# ethusb.net
KiCad netlist of a schematic drawn in Altium Designer
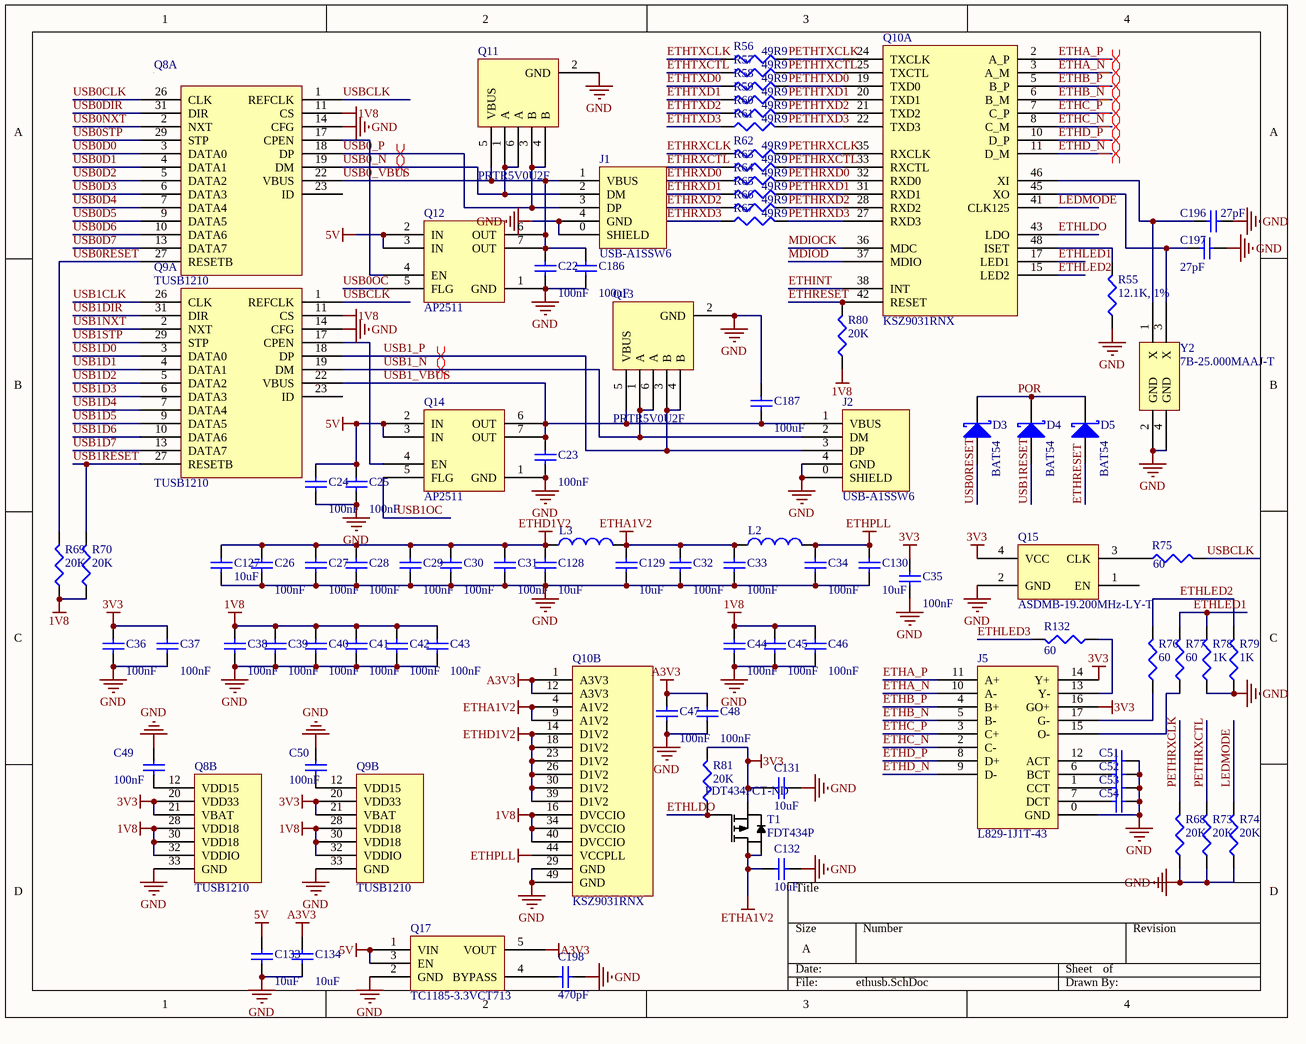
[diagram p0: ethusb.SchDoc]

(export (version "E")
  (design (tool "Eeschema 10.0.6"))
  (components
    (comp (ref "C22")
      (value "100nF")
      (footprint "CAPC1005X06L")
      (description "Capacitor")
      (fields (field (name "Comment") "Cap") (field (name "PUBLISHER") "Altium Limited"))
      (libsource (lib "Miscellaneous Devices") (part "Cap"))
    )
    (comp (ref "C23")
      (value "100nF")
      (footprint "CAPC1005X06L")
      (description "Capacitor")
      (fields (field (name "Comment") "Cap") (field (name "PUBLISHER") "Altium Limited"))
      (libsource (lib "Miscellaneous Devices") (part "Cap"))
    )
    (comp (ref "C24")
      (value "100nF")
      (footprint "CAPC1005X06L")
      (description "Capacitor")
      (fields (field (name "Comment") "Cap") (field (name "PUBLISHER") "Altium Limited"))
      (libsource (lib "Miscellaneous Devices") (part "Cap"))
    )
    (comp (ref "C25")
      (value "100nF")
      (footprint "CAPC1005X06L")
      (description "Capacitor")
      (fields (field (name "Comment") "Cap") (field (name "PUBLISHER") "Altium Limited"))
      (libsource (lib "Miscellaneous Devices") (part "Cap"))
    )
    (comp (ref "C26")
      (value "100nF")
      (footprint "CAPC1005X06L")
      (description "Capacitor")
      (fields (field (name "Comment") "Cap") (field (name "PUBLISHER") "Altium Limited"))
      (libsource (lib "Miscellaneous Devices") (part "Cap"))
    )
    (comp (ref "C27")
      (value "100nF")
      (footprint "CAPC1005X06L")
      (description "Capacitor")
      (fields (field (name "Comment") "Cap") (field (name "PUBLISHER") "Altium Limited"))
      (libsource (lib "Miscellaneous Devices") (part "Cap"))
    )
    (comp (ref "C28")
      (value "100nF")
      (footprint "CAPC1005X06L")
      (description "Capacitor")
      (fields (field (name "Comment") "Cap") (field (name "PUBLISHER") "Altium Limited"))
      (libsource (lib "Miscellaneous Devices") (part "Cap"))
    )
    (comp (ref "C29")
      (value "100nF")
      (footprint "CAPC1005X06L")
      (description "Capacitor")
      (fields (field (name "Comment") "Cap") (field (name "PUBLISHER") "Altium Limited"))
      (libsource (lib "Miscellaneous Devices") (part "Cap"))
    )
    (comp (ref "C30")
      (value "100nF")
      (footprint "CAPC1005X06L")
      (description "Capacitor")
      (fields (field (name "Comment") "Cap") (field (name "PUBLISHER") "Altium Limited"))
      (libsource (lib "Miscellaneous Devices") (part "Cap"))
    )
    (comp (ref "C31")
      (value "100nF")
      (footprint "CAPC1005X06L")
      (description "Capacitor")
      (fields (field (name "Comment") "Cap") (field (name "PUBLISHER") "Altium Limited"))
      (libsource (lib "Miscellaneous Devices") (part "Cap"))
    )
    (comp (ref "C32")
      (value "100nF")
      (footprint "CAPC1005X06L")
      (description "Capacitor")
      (fields (field (name "Comment") "Cap") (field (name "PUBLISHER") "Altium Limited"))
      (libsource (lib "Miscellaneous Devices") (part "Cap"))
    )
    (comp (ref "C33")
      (value "100nF")
      (footprint "CAPC1005X06L")
      (description "Capacitor")
      (fields (field (name "Comment") "Cap") (field (name "PUBLISHER") "Altium Limited"))
      (libsource (lib "Miscellaneous Devices") (part "Cap"))
    )
    (comp (ref "C34")
      (value "100nF")
      (footprint "CAPC1005X06L")
      (description "Capacitor")
      (fields (field (name "Comment") "Cap") (field (name "PUBLISHER") "Altium Limited"))
      (libsource (lib "Miscellaneous Devices") (part "Cap"))
    )
    (comp (ref "C35")
      (value "100nF")
      (footprint "CAPC1005X06L")
      (description "Capacitor")
      (fields (field (name "Comment") "Cap") (field (name "PUBLISHER") "Altium Limited"))
      (libsource (lib "Miscellaneous Devices") (part "Cap"))
    )
    (comp (ref "C36")
      (value "100nF")
      (footprint "CAPC1005X06L")
      (description "Capacitor")
      (fields (field (name "Comment") "Cap") (field (name "PUBLISHER") "Altium Limited"))
      (libsource (lib "Miscellaneous Devices") (part "Cap"))
    )
    (comp (ref "C37")
      (value "100nF")
      (footprint "CAPC1005X06L")
      (description "Capacitor")
      (fields (field (name "Comment") "Cap") (field (name "PUBLISHER") "Altium Limited"))
      (libsource (lib "Miscellaneous Devices") (part "Cap"))
    )
    (comp (ref "C38")
      (value "100nF")
      (footprint "CAPC1005X06L")
      (description "Capacitor")
      (fields (field (name "Comment") "Cap") (field (name "PUBLISHER") "Altium Limited"))
      (libsource (lib "Miscellaneous Devices") (part "Cap"))
    )
    (comp (ref "C39")
      (value "100nF")
      (footprint "CAPC1005X06L")
      (description "Capacitor")
      (fields (field (name "Comment") "Cap") (field (name "PUBLISHER") "Altium Limited"))
      (libsource (lib "Miscellaneous Devices") (part "Cap"))
    )
    (comp (ref "C40")
      (value "100nF")
      (footprint "CAPC1005X06L")
      (description "Capacitor")
      (fields (field (name "Comment") "Cap") (field (name "PUBLISHER") "Altium Limited"))
      (libsource (lib "Miscellaneous Devices") (part "Cap"))
    )
    (comp (ref "C41")
      (value "100nF")
      (footprint "CAPC1005X06L")
      (description "Capacitor")
      (fields (field (name "Comment") "Cap") (field (name "PUBLISHER") "Altium Limited"))
      (libsource (lib "Miscellaneous Devices") (part "Cap"))
    )
    (comp (ref "C42")
      (value "100nF")
      (footprint "CAPC1005X06L")
      (description "Capacitor")
      (fields (field (name "Comment") "Cap") (field (name "PUBLISHER") "Altium Limited"))
      (libsource (lib "Miscellaneous Devices") (part "Cap"))
    )
    (comp (ref "C43")
      (value "100nF")
      (footprint "CAPC1005X06L")
      (description "Capacitor")
      (fields (field (name "Comment") "Cap") (field (name "PUBLISHER") "Altium Limited"))
      (libsource (lib "Miscellaneous Devices") (part "Cap"))
    )
    (comp (ref "C44")
      (value "100nF")
      (footprint "CAPC1005X06L")
      (description "Capacitor")
      (fields (field (name "Comment") "Cap") (field (name "PUBLISHER") "Altium Limited"))
      (libsource (lib "Miscellaneous Devices") (part "Cap"))
    )
    (comp (ref "C45")
      (value "100nF")
      (footprint "CAPC1005X06L")
      (description "Capacitor")
      (fields (field (name "Comment") "Cap") (field (name "PUBLISHER") "Altium Limited"))
      (libsource (lib "Miscellaneous Devices") (part "Cap"))
    )
    (comp (ref "C46")
      (value "100nF")
      (footprint "CAPC1005X06L")
      (description "Capacitor")
      (fields (field (name "Comment") "Cap") (field (name "PUBLISHER") "Altium Limited"))
      (libsource (lib "Miscellaneous Devices") (part "Cap"))
    )
    (comp (ref "C47")
      (value "100nF")
      (footprint "CAPC1005X06L")
      (description "Capacitor")
      (fields (field (name "Comment") "Cap") (field (name "PUBLISHER") "Altium Limited"))
      (libsource (lib "Miscellaneous Devices") (part "Cap"))
    )
    (comp (ref "C48")
      (value "100nF")
      (footprint "CAPC1005X06L")
      (description "Capacitor")
      (fields (field (name "Comment") "Cap") (field (name "PUBLISHER") "Altium Limited"))
      (libsource (lib "Miscellaneous Devices") (part "Cap"))
    )
    (comp (ref "C49")
      (value "100nF")
      (footprint "CAPC1005X06L")
      (description "Capacitor")
      (fields (field (name "Comment") "Cap") (field (name "PUBLISHER") "Altium Limited"))
      (libsource (lib "Miscellaneous Devices") (part "Cap"))
    )
    (comp (ref "C50")
      (value "100nF")
      (footprint "CAPC1005X06L")
      (description "Capacitor")
      (fields (field (name "Comment") "Cap") (field (name "PUBLISHER") "Altium Limited"))
      (libsource (lib "Miscellaneous Devices") (part "Cap"))
    )
    (comp (ref "C51")
      (value "Cap")
      (footprint "CAPC1005X06L")
      (description "Capacitor")
      (fields (field (name "PUBLISHER") "Altium Limited"))
      (libsource (lib "Miscellaneous Devices") (part "Cap"))
    )
    (comp (ref "C52")
      (value "Cap")
      (footprint "CAPC1005X06L")
      (description "Capacitor")
      (fields (field (name "PUBLISHER") "Altium Limited"))
      (libsource (lib "Miscellaneous Devices") (part "Cap"))
    )
    (comp (ref "C53")
      (value "Cap")
      (footprint "CAPC1005X06L")
      (description "Capacitor")
      (fields (field (name "PUBLISHER") "Altium Limited"))
      (libsource (lib "Miscellaneous Devices") (part "Cap"))
    )
    (comp (ref "C54")
      (value "Cap")
      (footprint "CAPC1005X06L")
      (description "Capacitor")
      (fields (field (name "PUBLISHER") "Altium Limited"))
      (libsource (lib "Miscellaneous Devices") (part "Cap"))
    )
    (comp (ref "C127")
      (value "10uF")
      (footprint "CAPC1608X90N")
      (description "Capacitor")
      (fields (field (name "Comment") "GRM188R60G106ME47") (field (name "PUBLISHER") "Altium Limited"))
      (libsource (lib "Miscellaneous Devices") (part "Cap"))
    )
    (comp (ref "C128")
      (value "10uF")
      (footprint "CAPC1608X90N")
      (description "Capacitor")
      (fields (field (name "Comment") "GRM188R60G106ME47") (field (name "PUBLISHER") "Altium Limited"))
      (libsource (lib "Miscellaneous Devices") (part "Cap"))
    )
    (comp (ref "C129")
      (value "10uF")
      (footprint "CAPC1608X90N")
      (description "Capacitor")
      (fields (field (name "Comment") "GRM188R60G106ME47") (field (name "PUBLISHER") "Altium Limited"))
      (libsource (lib "Miscellaneous Devices") (part "Cap"))
    )
    (comp (ref "C130")
      (value "10uF")
      (footprint "CAPC1608X90N")
      (description "Capacitor")
      (fields (field (name "Comment") "GRM188R60G106ME47") (field (name "PUBLISHER") "Altium Limited"))
      (libsource (lib "Miscellaneous Devices") (part "Cap"))
    )
    (comp (ref "C131")
      (value "10uF")
      (footprint "CAPC1608X90N")
      (description "Capacitor")
      (fields (field (name "Comment") "GRM188R60G106ME47") (field (name "PUBLISHER") "Altium Limited"))
      (libsource (lib "Miscellaneous Devices") (part "Cap"))
    )
    (comp (ref "C132")
      (value "10uF")
      (footprint "CAPC1608X90N")
      (description "Capacitor")
      (fields (field (name "Comment") "GRM188R60G106ME47") (field (name "PUBLISHER") "Altium Limited"))
      (libsource (lib "Miscellaneous Devices") (part "Cap"))
    )
    (comp (ref "C133")
      (value "10uF")
      (footprint "CAPC1608X90N")
      (description "Capacitor")
      (fields (field (name "Comment") "GRM188R60G106ME47") (field (name "PUBLISHER") "Altium Limited"))
      (libsource (lib "Miscellaneous Devices") (part "Cap"))
    )
    (comp (ref "C134")
      (value "10uF")
      (footprint "CAPC1608X90N")
      (description "Capacitor")
      (fields (field (name "Comment") "GRM188R60G106ME47") (field (name "PUBLISHER") "Altium Limited"))
      (libsource (lib "Miscellaneous Devices") (part "Cap"))
    )
    (comp (ref "C186")
      (value "100uF")
      (footprint "CAPC3225X220N")
      (description "Capacitor")
      (fields (field (name "Comment") "GRM31CR60J107ME39L") (field (name "PUBLISHER") "Altium Limited"))
      (libsource (lib "Miscellaneous Devices") (part "Cap"))
    )
    (comp (ref "C187")
      (value "100uF")
      (footprint "CAPC3225X220N")
      (description "Capacitor")
      (fields (field (name "Comment") "GRM31CR60J107ME39L") (field (name "PUBLISHER") "Altium Limited"))
      (libsource (lib "Miscellaneous Devices") (part "Cap"))
    )
    (comp (ref "C196")
      (value "27pF")
      (footprint "CAPC1608X90N")
      (description "Capacitor")
      (fields (field (name "Comment") "CL10C270JB8NNNC") (field (name "PUBLISHER") "Altium Limited"))
      (libsource (lib "Miscellaneous Devices") (part "Cap"))
    )
    (comp (ref "C197")
      (value "27pF")
      (footprint "CAPC1608X90N")
      (description "Capacitor")
      (fields (field (name "Comment") "CL10C270JB8NNNC") (field (name "PUBLISHER") "Altium Limited"))
      (libsource (lib "Miscellaneous Devices") (part "Cap"))
    )
    (comp (ref "C198")
      (value "470pF")
      (footprint "CAPC1608X90N")
      (description "Capacitor")
      (fields (field (name "Comment") "CL10C471JB8NCNC") (field (name "PUBLISHER") "Altium Limited"))
      (libsource (lib "Miscellaneous Devices") (part "Cap"))
    )
    (comp (ref "D3")
      (value "BAT54")
      (footprint "BAT54")
      (description "Schottky Diode")
      (fields (field (name "PUBLISHER") "Altium Limited"))
      (libsource (lib "Miscellaneous Devices") (part "D Schottky"))
    )
    (comp (ref "D4")
      (value "BAT54")
      (footprint "BAT54")
      (description "Schottky Diode")
      (fields (field (name "PUBLISHER") "Altium Limited"))
      (libsource (lib "Miscellaneous Devices") (part "D Schottky"))
    )
    (comp (ref "D5")
      (value "BAT54")
      (footprint "BAT54")
      (description "Schottky Diode")
      (fields (field (name "PUBLISHER") "Altium Limited"))
      (libsource (lib "Miscellaneous Devices") (part "D Schottky"))
    )
    (comp (ref "J1") (value "USB-A1SSW6") (footprint "USB-A1SSW6") (libsource (lib "schlib") (part "USB")))
    (comp (ref "J2") (value "USB-A1SSW6") (footprint "USB-A1SSW6") (libsource (lib "schlib") (part "USB")))
    (comp (ref "J5")
      (value "L829-1J1T-43")
      (footprint "ETH-L829-1J1T-43")
      (libsource (lib "schlib") (part "ETH"))
    )
    (comp (ref "L2")
      (value "BLM18SG121TN1")
      (footprint "CAPC1608X90N")
      (description "Inductor")
      (fields (field (name "PUBLISHER") "Altium Limited"))
      (libsource (lib "Miscellaneous Devices") (part "Inductor"))
    )
    (comp (ref "L3")
      (value "BLM18SG121TN1")
      (footprint "CAPC1608X90N")
      (description "Inductor")
      (fields (field (name "PUBLISHER") "Altium Limited"))
      (libsource (lib "Miscellaneous Devices") (part "Inductor"))
    )
    (comp (ref "Q8")
      (value "TUSB1210")
      (footprint "QFN50P500X500X80_HS-33N")
      (libsource (lib "schlib") (part "TUSB1210"))
    )
    (comp (ref "Q9")
      (value "TUSB1210")
      (footprint "QFN50P500X500X80_HS-33N")
      (libsource (lib "schlib") (part "TUSB1210"))
    )
    (comp (ref "Q10") (value "KSZ9031RNX") (libsource (lib "schlib") (part "KSZ9031RNX")))
    (comp (ref "Q11")
      (value "PRTR5V0U2F")
      (footprint "SOT886")
      (libsource (lib "schlib") (part "PRTR5V0U2F"))
    )
    (comp (ref "Q12")
      (value "AP2511")
      (footprint "SOIC127P600X175-8AN")
      (libsource (lib "schlib") (part "AP2511"))
    )
    (comp (ref "Q13")
      (value "PRTR5V0U2F")
      (footprint "SOT886")
      (libsource (lib "schlib") (part "PRTR5V0U2F"))
    )
    (comp (ref "Q14")
      (value "AP2511")
      (footprint "SOIC127P600X175-8AN")
      (libsource (lib "schlib") (part "AP2511"))
    )
    (comp (ref "Q15")
      (value "ASDMB-19.200MHz-LY-T")
      (footprint "ASDMB")
      (libsource (lib "schlib") (part "osc"))
    )
    (comp (ref "Q17")
      (value "TC1185-3.3VCT713")
      (footprint "SOT23-5")
      (libsource (lib "schlib") (part "LDO"))
    )
    (comp (ref "R55")
      (value "12.1K, 1%")
      (footprint "J1-0603")
      (description "Resistor")
      (fields (field (name "Comment") "RC1608F1212CS") (field (name "PUBLISHER") "Altium Limited"))
      (libsource (lib "Miscellaneous Devices") (part "Res3"))
    )
    (comp (ref "R56")
      (value "49R9")
      (footprint "CAPC1005X06L")
      (description "Resistor")
      (fields (field (name "Comment") "RC1005F49R9CS") (field (name "PUBLISHER") "Altium Limited"))
      (libsource (lib "Miscellaneous Devices") (part "Res3"))
    )
    (comp (ref "R57")
      (value "49R9")
      (footprint "CAPC1005X06L")
      (description "Resistor")
      (fields (field (name "Comment") "RC1005F49R9CS") (field (name "PUBLISHER") "Altium Limited"))
      (libsource (lib "Miscellaneous Devices") (part "Res3"))
    )
    (comp (ref "R58")
      (value "49R9")
      (footprint "CAPC1005X06L")
      (description "Resistor")
      (fields (field (name "Comment") "RC1005F49R9CS") (field (name "PUBLISHER") "Altium Limited"))
      (libsource (lib "Miscellaneous Devices") (part "Res3"))
    )
    (comp (ref "R59")
      (value "49R9")
      (footprint "CAPC1005X06L")
      (description "Resistor")
      (fields (field (name "Comment") "RC1005F49R9CS") (field (name "PUBLISHER") "Altium Limited"))
      (libsource (lib "Miscellaneous Devices") (part "Res3"))
    )
    (comp (ref "R60")
      (value "49R9")
      (footprint "CAPC1005X06L")
      (description "Resistor")
      (fields (field (name "Comment") "RC1005F49R9CS") (field (name "PUBLISHER") "Altium Limited"))
      (libsource (lib "Miscellaneous Devices") (part "Res3"))
    )
    (comp (ref "R61")
      (value "49R9")
      (footprint "CAPC1005X06L")
      (description "Resistor")
      (fields (field (name "Comment") "RC1005F49R9CS") (field (name "PUBLISHER") "Altium Limited"))
      (libsource (lib "Miscellaneous Devices") (part "Res3"))
    )
    (comp (ref "R62")
      (value "49R9")
      (footprint "CAPC1005X06L")
      (description "Resistor")
      (fields (field (name "Comment") "RC1005F49R9CS") (field (name "PUBLISHER") "Altium Limited"))
      (libsource (lib "Miscellaneous Devices") (part "Res3"))
    )
    (comp (ref "R63")
      (value "49R9")
      (footprint "CAPC1005X06L")
      (description "Resistor")
      (fields (field (name "Comment") "RC1005F49R9CS") (field (name "PUBLISHER") "Altium Limited"))
      (libsource (lib "Miscellaneous Devices") (part "Res3"))
    )
    (comp (ref "R64")
      (value "49R9")
      (footprint "CAPC1005X06L")
      (description "Resistor")
      (fields (field (name "Comment") "RC1005F49R9CS") (field (name "PUBLISHER") "Altium Limited"))
      (libsource (lib "Miscellaneous Devices") (part "Res3"))
    )
    (comp (ref "R65")
      (value "49R9")
      (footprint "CAPC1005X06L")
      (description "Resistor")
      (fields (field (name "Comment") "RC1005F49R9CS") (field (name "PUBLISHER") "Altium Limited"))
      (libsource (lib "Miscellaneous Devices") (part "Res3"))
    )
    (comp (ref "R66")
      (value "49R9")
      (footprint "CAPC1005X06L")
      (description "Resistor")
      (fields (field (name "Comment") "RC1005F49R9CS") (field (name "PUBLISHER") "Altium Limited"))
      (libsource (lib "Miscellaneous Devices") (part "Res3"))
    )
    (comp (ref "R67")
      (value "49R9")
      (footprint "CAPC1005X06L")
      (description "Resistor")
      (fields (field (name "Comment") "RC1005F49R9CS") (field (name "PUBLISHER") "Altium Limited"))
      (libsource (lib "Miscellaneous Devices") (part "Res3"))
    )
    (comp (ref "R68")
      (value "20K")
      (footprint "J1-0603")
      (description "Resistor")
      (fields (field (name "Comment") "RC1608F203CS") (field (name "PUBLISHER") "Altium Limited"))
      (libsource (lib "Miscellaneous Devices") (part "Res3"))
    )
    (comp (ref "R69")
      (value "20K")
      (footprint "J1-0603")
      (description "Resistor")
      (fields (field (name "Comment") "RC1608F203CS") (field (name "PUBLISHER") "Altium Limited"))
      (libsource (lib "Miscellaneous Devices") (part "Res3"))
    )
    (comp (ref "R70")
      (value "20K")
      (footprint "J1-0603")
      (description "Resistor")
      (fields (field (name "Comment") "RC1608F203CS") (field (name "PUBLISHER") "Altium Limited"))
      (libsource (lib "Miscellaneous Devices") (part "Res3"))
    )
    (comp (ref "R73")
      (value "20K")
      (footprint "J1-0603")
      (description "Resistor")
      (fields (field (name "Comment") "RC1608F203CS") (field (name "PUBLISHER") "Altium Limited"))
      (libsource (lib "Miscellaneous Devices") (part "Res3"))
    )
    (comp (ref "R74")
      (value "20K")
      (footprint "J1-0603")
      (description "Resistor")
      (fields (field (name "Comment") "RC1608F203CS") (field (name "PUBLISHER") "Altium Limited"))
      (libsource (lib "Miscellaneous Devices") (part "Res3"))
    )
    (comp (ref "R75")
      (value "60")
      (footprint "J1-0603")
      (description "Resistor")
      (fields (field (name "Comment") "RC1608F60R4CS"))
      (libsource (lib "Miscellaneous Devices") (part "Res3"))
    )
    (comp (ref "R76")
      (value "60")
      (footprint "J1-0603")
      (description "Resistor")
      (fields (field (name "Comment") "RC1608F60R4CS"))
      (libsource (lib "Miscellaneous Devices") (part "Res3"))
    )
    (comp (ref "R77")
      (value "60")
      (footprint "J1-0603")
      (description "Resistor")
      (fields (field (name "Comment") "RC1608F60R4CS"))
      (libsource (lib "Miscellaneous Devices") (part "Res3"))
    )
    (comp (ref "R78")
      (value "1K")
      (footprint "J1-0603")
      (description "Resistor")
      (fields (field (name "Comment") "RC1608J102CS"))
      (libsource (lib "Miscellaneous Devices") (part "Res3"))
    )
    (comp (ref "R79")
      (value "1K")
      (footprint "J1-0603")
      (description "Resistor")
      (fields (field (name "Comment") "RC1608J102CS"))
      (libsource (lib "Miscellaneous Devices") (part "Res3"))
    )
    (comp (ref "R80")
      (value "20K")
      (footprint "J1-0603")
      (description "Resistor")
      (fields (field (name "Comment") "RC1608F203CS"))
      (libsource (lib "Miscellaneous Devices") (part "Res3"))
    )
    (comp (ref "R81")
      (value "20K")
      (footprint "J1-0603")
      (description "Resistor")
      (fields (field (name "Comment") "RC1608F203CS"))
      (libsource (lib "Miscellaneous Devices") (part "Res3"))
    )
    (comp (ref "R132")
      (value "60")
      (footprint "J1-0603")
      (description "Resistor")
      (fields (field (name "Comment") "RC1608F60R4CS"))
      (libsource (lib "Miscellaneous Devices") (part "Res3"))
    )
    (comp (ref "T1")
      (value "FDT434P")
      (fields (field (name "SUPPLIER PART NUMBER 1") "FDT434PCT-ND"))
      (libsource (lib "schlib") (part "PMOS4"))
    )
    (comp (ref "Y2") (value "7B-25.000MAAJ-T") (footprint "XTAL") (libsource (lib "schlib") (part "XTAL")))
  )
  (nets
    (net (code "1") (name "/ETHA_N") (class "Default")
      (node (ref "J5") (pin "10") (pinfunction "A-_10") (pintype "passive"))
      (node (ref "Q10") (pin "3") (pinfunction "A_M_3") (pintype "passive"))
    )
    (net (code "2") (name "/ETHA_P") (class "Default")
      (node (ref "J5") (pin "11") (pinfunction "A+_11") (pintype "passive"))
      (node (ref "Q10") (pin "2") (pinfunction "A_P_2") (pintype "passive"))
    )
    (net (code "3") (name "/ETHB_N") (class "Default")
      (node (ref "J5") (pin "5") (pinfunction "B-_5") (pintype "passive"))
      (node (ref "Q10") (pin "6") (pinfunction "B_M_6") (pintype "passive"))
    )
    (net (code "4") (name "/ETHB_P") (class "Default")
      (node (ref "J5") (pin "4") (pinfunction "B+_4") (pintype "passive"))
      (node (ref "Q10") (pin "5") (pinfunction "B_P_5") (pintype "passive"))
    )
    (net (code "5") (name "/ETHC_N") (class "Default")
      (node (ref "J5") (pin "2") (pinfunction "C-_2") (pintype "passive"))
      (node (ref "Q10") (pin "8") (pinfunction "C_M_8") (pintype "passive"))
    )
    (net (code "6") (name "/ETHC_P") (class "Default")
      (node (ref "J5") (pin "3") (pinfunction "C+_3") (pintype "passive"))
      (node (ref "Q10") (pin "7") (pinfunction "C_P_7") (pintype "passive"))
    )
    (net (code "7") (name "/ETHD_N") (class "Default")
      (node (ref "J5") (pin "9") (pinfunction "D-_9") (pintype "passive"))
      (node (ref "Q10") (pin "11") (pinfunction "D_M_11") (pintype "passive"))
    )
    (net (code "8") (name "/ETHD_P") (class "Default")
      (node (ref "J5") (pin "8") (pinfunction "D+_8") (pintype "passive"))
      (node (ref "Q10") (pin "10") (pinfunction "D_P_10") (pintype "passive"))
    )
    (net (code "9") (name "/ETHINT") (class "Default")
      (node (ref "Q10") (pin "38") (pinfunction "INT_38") (pintype "passive"))
    )
    (net (code "10") (name "/ETHLDO") (class "Default")
      (node (ref "Q10") (pin "43") (pinfunction "LDO_43") (pintype "passive"))
      (node (ref "R81") (pin "1") (pinfunction "1_1") (pintype "passive"))
      (node (ref "T1") (pin "1") (pinfunction "G_1") (pintype "passive"))
    )
    (net (code "11") (name "/ETHLED1") (class "Default")
      (node (ref "Q10") (pin "17") (pinfunction "LED1_17") (pintype "passive"))
      (node (ref "R77") (pin "2") (pinfunction "2_2") (pintype "passive"))
      (node (ref "R78") (pin "2") (pinfunction "2_2") (pintype "passive"))
    )
    (net (code "12") (name "/ETHLED2") (class "Default")
      (node (ref "Q10") (pin "15") (pinfunction "LED2_15") (pintype "passive"))
      (node (ref "R76") (pin "2") (pinfunction "2_2") (pintype "passive"))
      (node (ref "R79") (pin "2") (pinfunction "2_2") (pintype "passive"))
    )
    (net (code "13") (name "/ETHLED3") (class "Default")
      (node (ref "R132") (pin "2") (pinfunction "2_2") (pintype "passive"))
    )
    (net (code "14") (name "/ETHRESET") (class "Default")
      (node (ref "D5") (pin "1") (pinfunction "A_1") (pintype "passive"))
      (node (ref "Q10") (pin "42") (pinfunction "RESET_42") (pintype "passive"))
      (node (ref "R80") (pin "2") (pinfunction "2_2") (pintype "passive"))
    )
    (net (code "15") (name "/ETHRXCLK") (class "Default")
      (node (ref "R62") (pin "1") (pinfunction "1_1") (pintype "passive"))
    )
    (net (code "16") (name "/ETHRXCTL") (class "Default")
      (node (ref "R63") (pin "1") (pinfunction "1_1") (pintype "passive"))
    )
    (net (code "17") (name "/ETHRXD0") (class "Default")
      (node (ref "R64") (pin "1") (pinfunction "1_1") (pintype "passive"))
    )
    (net (code "18") (name "/ETHRXD1") (class "Default")
      (node (ref "R65") (pin "1") (pinfunction "1_1") (pintype "passive"))
    )
    (net (code "19") (name "/ETHRXD2") (class "Default")
      (node (ref "R66") (pin "1") (pinfunction "1_1") (pintype "passive"))
    )
    (net (code "20") (name "/ETHRXD3") (class "Default")
      (node (ref "R67") (pin "1") (pinfunction "1_1") (pintype "passive"))
    )
    (net (code "21") (name "/ETHTXCLK") (class "Default")
      (node (ref "R56") (pin "1") (pinfunction "1_1") (pintype "passive"))
    )
    (net (code "22") (name "/ETHTXCTL") (class "Default")
      (node (ref "R57") (pin "1") (pinfunction "1_1") (pintype "passive"))
    )
    (net (code "23") (name "/ETHTXD0") (class "Default")
      (node (ref "R58") (pin "1") (pinfunction "1_1") (pintype "passive"))
    )
    (net (code "24") (name "/ETHTXD1") (class "Default")
      (node (ref "R59") (pin "1") (pinfunction "1_1") (pintype "passive"))
    )
    (net (code "25") (name "/ETHTXD2") (class "Default")
      (node (ref "R60") (pin "1") (pinfunction "1_1") (pintype "passive"))
    )
    (net (code "26") (name "/ETHTXD3") (class "Default")
      (node (ref "R61") (pin "1") (pinfunction "1_1") (pintype "passive"))
    )
    (net (code "27") (name "/LEDMODE") (class "Default")
      (node (ref "Q10") (pin "41") (pinfunction "CLK125_41") (pintype "passive"))
      (node (ref "R74") (pin "2") (pinfunction "2_2") (pintype "passive"))
    )
    (net (code "28") (name "/MDIOCK") (class "Default")
      (node (ref "Q10") (pin "36") (pinfunction "MDC_36") (pintype "passive"))
    )
    (net (code "29") (name "/MDIOD") (class "Default")
      (node (ref "Q10") (pin "37") (pinfunction "MDIO_37") (pintype "passive"))
    )
    (net (code "30") (name "/PETHRXCLK") (class "Default")
      (node (ref "Q10") (pin "35") (pinfunction "RXCLK_35") (pintype "passive"))
      (node (ref "R62") (pin "2") (pinfunction "2_2") (pintype "passive"))
      (node (ref "R68") (pin "2") (pinfunction "2_2") (pintype "passive"))
    )
    (net (code "31") (name "/PETHRXCTL") (class "Default")
      (node (ref "Q10") (pin "33") (pinfunction "RXCTL_33") (pintype "passive"))
      (node (ref "R63") (pin "2") (pinfunction "2_2") (pintype "passive"))
      (node (ref "R73") (pin "2") (pinfunction "2_2") (pintype "passive"))
    )
    (net (code "32") (name "/PETHRXD0") (class "Default")
      (node (ref "Q10") (pin "32") (pinfunction "RXD0_32") (pintype "passive"))
      (node (ref "R64") (pin "2") (pinfunction "2_2") (pintype "passive"))
    )
    (net (code "33") (name "/PETHRXD1") (class "Default")
      (node (ref "Q10") (pin "31") (pinfunction "RXD1_31") (pintype "passive"))
      (node (ref "R65") (pin "2") (pinfunction "2_2") (pintype "passive"))
    )
    (net (code "34") (name "/PETHRXD2") (class "Default")
      (node (ref "Q10") (pin "28") (pinfunction "RXD2_28") (pintype "passive"))
      (node (ref "R66") (pin "2") (pinfunction "2_2") (pintype "passive"))
    )
    (net (code "35") (name "/PETHRXD3") (class "Default")
      (node (ref "Q10") (pin "27") (pinfunction "RXD3_27") (pintype "passive"))
      (node (ref "R67") (pin "2") (pinfunction "2_2") (pintype "passive"))
    )
    (net (code "36") (name "/PETHTXCLK") (class "Default")
      (node (ref "Q10") (pin "24") (pinfunction "TXCLK_24") (pintype "passive"))
      (node (ref "R56") (pin "2") (pinfunction "2_2") (pintype "passive"))
    )
    (net (code "37") (name "/PETHTXCTL") (class "Default")
      (node (ref "Q10") (pin "25") (pinfunction "TXCTL_25") (pintype "passive"))
      (node (ref "R57") (pin "2") (pinfunction "2_2") (pintype "passive"))
    )
    (net (code "38") (name "/PETHTXD0") (class "Default")
      (node (ref "Q10") (pin "19") (pinfunction "TXD0_19") (pintype "passive"))
      (node (ref "R58") (pin "2") (pinfunction "2_2") (pintype "passive"))
    )
    (net (code "39") (name "/PETHTXD1") (class "Default")
      (node (ref "Q10") (pin "20") (pinfunction "TXD1_20") (pintype "passive"))
      (node (ref "R59") (pin "2") (pinfunction "2_2") (pintype "passive"))
    )
    (net (code "40") (name "/PETHTXD2") (class "Default")
      (node (ref "Q10") (pin "21") (pinfunction "TXD2_21") (pintype "passive"))
      (node (ref "R60") (pin "2") (pinfunction "2_2") (pintype "passive"))
    )
    (net (code "41") (name "/PETHTXD3") (class "Default")
      (node (ref "Q10") (pin "22") (pinfunction "TXD3_22") (pintype "passive"))
      (node (ref "R61") (pin "2") (pinfunction "2_2") (pintype "passive"))
    )
    (net (code "42") (name "/POR") (class "Default")
      (node (ref "D3") (pin "2") (pinfunction "K_2") (pintype "passive"))
      (node (ref "D4") (pin "2") (pinfunction "K_2") (pintype "passive"))
      (node (ref "D5") (pin "2") (pinfunction "K_2") (pintype "passive"))
    )
    (net (code "43") (name "/USB0CLK") (class "Default")
      (node (ref "Q8") (pin "26") (pinfunction "CLK_26") (pintype "passive"))
    )
    (net (code "44") (name "/USB0D0") (class "Default")
      (node (ref "Q8") (pin "3") (pinfunction "DATA0_3") (pintype "passive"))
    )
    (net (code "45") (name "/USB0D1") (class "Default")
      (node (ref "Q8") (pin "4") (pinfunction "DATA1_4") (pintype "passive"))
    )
    (net (code "46") (name "/USB0D2") (class "Default")
      (node (ref "Q8") (pin "5") (pinfunction "DATA2_5") (pintype "passive"))
    )
    (net (code "47") (name "/USB0D3") (class "Default")
      (node (ref "Q8") (pin "6") (pinfunction "DATA3_6") (pintype "passive"))
    )
    (net (code "48") (name "/USB0D4") (class "Default")
      (node (ref "Q8") (pin "7") (pinfunction "DATA4_7") (pintype "passive"))
    )
    (net (code "49") (name "/USB0D5") (class "Default")
      (node (ref "Q8") (pin "9") (pinfunction "DATA5_9") (pintype "passive"))
    )
    (net (code "50") (name "/USB0D6") (class "Default")
      (node (ref "Q8") (pin "10") (pinfunction "DATA6_10") (pintype "passive"))
    )
    (net (code "51") (name "/USB0D7") (class "Default")
      (node (ref "Q8") (pin "13") (pinfunction "DATA7_13") (pintype "passive"))
    )
    (net (code "52") (name "/USB0DIR") (class "Default")
      (node (ref "Q8") (pin "31") (pinfunction "DIR_31") (pintype "passive"))
    )
    (net (code "53") (name "/USB0NXT") (class "Default")
      (node (ref "Q8") (pin "2") (pinfunction "NXT_2") (pintype "passive"))
    )
    (net (code "54") (name "/USB0OC") (class "Default")
      (node (ref "Q12") (pin "5") (pinfunction "FLG_5") (pintype "passive"))
    )
    (net (code "55") (name "/USB0RESET") (class "Default")
      (node (ref "D3") (pin "1") (pinfunction "A_1") (pintype "passive"))
      (node (ref "Q8") (pin "27") (pinfunction "RESETB_27") (pintype "passive"))
      (node (ref "R69") (pin "2") (pinfunction "2_2") (pintype "passive"))
    )
    (net (code "56") (name "/USB0STP") (class "Default")
      (node (ref "Q8") (pin "29") (pinfunction "STP_29") (pintype "passive"))
    )
    (net (code "57") (name "/USB0_N") (class "Default")
      (node (ref "J1") (pin "2") (pinfunction "DM_2") (pintype "passive"))
      (node (ref "Q11") (pin "1") (pinfunction "A_1") (pintype "passive"))
      (node (ref "Q11") (pin "6") (pinfunction "A_6") (pintype "passive"))
      (node (ref "Q8") (pin "19") (pinfunction "DM_19") (pintype "passive"))
    )
    (net (code "58") (name "/USB0_P") (class "Default")
      (node (ref "J1") (pin "3") (pinfunction "DP_3") (pintype "passive"))
      (node (ref "Q11") (pin "3") (pinfunction "B_3") (pintype "passive"))
      (node (ref "Q11") (pin "4") (pinfunction "B_4") (pintype "passive"))
      (node (ref "Q8") (pin "18") (pinfunction "DP_18") (pintype "passive"))
    )
    (net (code "59") (name "/USB0_VBUS") (class "Default")
      (node (ref "C186") (pin "2") (pinfunction "2_2") (pintype "passive"))
      (node (ref "C22") (pin "2") (pinfunction "2_2") (pintype "passive"))
      (node (ref "J1") (pin "1") (pinfunction "VBUS_1") (pintype "passive"))
      (node (ref "Q11") (pin "5") (pinfunction "VBUS_5") (pintype "passive"))
      (node (ref "Q12") (pin "6") (pinfunction "OUT_6") (pintype "passive"))
      (node (ref "Q12") (pin "7") (pinfunction "OUT_7") (pintype "passive"))
      (node (ref "Q8") (pin "22") (pinfunction "VBUS_22") (pintype "passive"))
    )
    (net (code "60") (name "/USB1CLK") (class "Default")
      (node (ref "Q9") (pin "26") (pinfunction "CLK_26") (pintype "passive"))
    )
    (net (code "61") (name "/USB1D0") (class "Default")
      (node (ref "Q9") (pin "3") (pinfunction "DATA0_3") (pintype "passive"))
    )
    (net (code "62") (name "/USB1D1") (class "Default")
      (node (ref "Q9") (pin "4") (pinfunction "DATA1_4") (pintype "passive"))
    )
    (net (code "63") (name "/USB1D2") (class "Default")
      (node (ref "Q9") (pin "5") (pinfunction "DATA2_5") (pintype "passive"))
    )
    (net (code "64") (name "/USB1D3") (class "Default")
      (node (ref "Q9") (pin "6") (pinfunction "DATA3_6") (pintype "passive"))
    )
    (net (code "65") (name "/USB1D4") (class "Default")
      (node (ref "Q9") (pin "7") (pinfunction "DATA4_7") (pintype "passive"))
    )
    (net (code "66") (name "/USB1D5") (class "Default")
      (node (ref "Q9") (pin "9") (pinfunction "DATA5_9") (pintype "passive"))
    )
    (net (code "67") (name "/USB1D6") (class "Default")
      (node (ref "Q9") (pin "10") (pinfunction "DATA6_10") (pintype "passive"))
    )
    (net (code "68") (name "/USB1D7") (class "Default")
      (node (ref "Q9") (pin "13") (pinfunction "DATA7_13") (pintype "passive"))
    )
    (net (code "69") (name "/USB1DIR") (class "Default")
      (node (ref "Q9") (pin "31") (pinfunction "DIR_31") (pintype "passive"))
    )
    (net (code "70") (name "/USB1NXT") (class "Default")
      (node (ref "Q9") (pin "2") (pinfunction "NXT_2") (pintype "passive"))
    )
    (net (code "71") (name "/USB1OC") (class "Default")
      (node (ref "Q14") (pin "5") (pinfunction "FLG_5") (pintype "passive"))
    )
    (net (code "72") (name "/USB1RESET") (class "Default")
      (node (ref "D4") (pin "1") (pinfunction "A_1") (pintype "passive"))
      (node (ref "Q9") (pin "27") (pinfunction "RESETB_27") (pintype "passive"))
      (node (ref "R70") (pin "2") (pinfunction "2_2") (pintype "passive"))
    )
    (net (code "73") (name "/USB1STP") (class "Default")
      (node (ref "Q9") (pin "29") (pinfunction "STP_29") (pintype "passive"))
    )
    (net (code "74") (name "/USB1_N") (class "Default")
      (node (ref "J2") (pin "2") (pinfunction "DM_2") (pintype "passive"))
      (node (ref "Q13") (pin "1") (pinfunction "A_1") (pintype "passive"))
      (node (ref "Q13") (pin "6") (pinfunction "A_6") (pintype "passive"))
      (node (ref "Q9") (pin "19") (pinfunction "DM_19") (pintype "passive"))
    )
    (net (code "75") (name "/USB1_P") (class "Default")
      (node (ref "J2") (pin "3") (pinfunction "DP_3") (pintype "passive"))
      (node (ref "Q13") (pin "3") (pinfunction "B_3") (pintype "passive"))
      (node (ref "Q13") (pin "4") (pinfunction "B_4") (pintype "passive"))
      (node (ref "Q9") (pin "18") (pinfunction "DP_18") (pintype "passive"))
    )
    (net (code "76") (name "/USB1_VBUS") (class "Default")
      (node (ref "C187") (pin "1") (pinfunction "1_1") (pintype "passive"))
      (node (ref "C23") (pin "2") (pinfunction "2_2") (pintype "passive"))
      (node (ref "J2") (pin "1") (pinfunction "VBUS_1") (pintype "passive"))
      (node (ref "Q13") (pin "5") (pinfunction "VBUS_5") (pintype "passive"))
      (node (ref "Q14") (pin "6") (pinfunction "OUT_6") (pintype "passive"))
      (node (ref "Q14") (pin "7") (pinfunction "OUT_7") (pintype "passive"))
      (node (ref "Q9") (pin "22") (pinfunction "VBUS_22") (pintype "passive"))
    )
    (net (code "77") (name "/USBCLK") (class "Default")
      (node (ref "Q8") (pin "1") (pinfunction "REFCLK_1") (pintype "passive"))
      (node (ref "Q9") (pin "1") (pinfunction "REFCLK_1") (pintype "passive"))
      (node (ref "R75") (pin "2") (pinfunction "2_2") (pintype "passive"))
    )
    (net (code "78") (name "1V8") (class "Default")
      (node (ref "C38") (pin "2") (pinfunction "2_2") (pintype "passive"))
      (node (ref "C39") (pin "2") (pinfunction "2_2") (pintype "passive"))
      (node (ref "C40") (pin "2") (pinfunction "2_2") (pintype "passive"))
      (node (ref "C41") (pin "2") (pinfunction "2_2") (pintype "passive"))
      (node (ref "C42") (pin "2") (pinfunction "2_2") (pintype "passive"))
      (node (ref "C43") (pin "2") (pinfunction "2_2") (pintype "passive"))
      (node (ref "C44") (pin "2") (pinfunction "2_2") (pintype "passive"))
      (node (ref "C45") (pin "2") (pinfunction "2_2") (pintype "passive"))
      (node (ref "C46") (pin "2") (pinfunction "2_2") (pintype "passive"))
      (node (ref "Q10") (pin "16") (pinfunction "DVCCIO_16") (pintype "passive"))
      (node (ref "Q10") (pin "34") (pinfunction "DVCCIO_34") (pintype "passive"))
      (node (ref "Q10") (pin "40") (pinfunction "DVCCIO_40") (pintype "passive"))
      (node (ref "Q8") (pin "11") (pinfunction "CS_11") (pintype "passive"))
      (node (ref "Q8") (pin "28") (pinfunction "VDD18_28") (pintype "passive"))
      (node (ref "Q8") (pin "30") (pinfunction "VDD18_30") (pintype "passive"))
      (node (ref "Q8") (pin "32") (pinfunction "VDDIO_32") (pintype "passive"))
      (node (ref "Q9") (pin "11") (pinfunction "CS_11") (pintype "passive"))
      (node (ref "Q9") (pin "28") (pinfunction "VDD18_28") (pintype "passive"))
      (node (ref "Q9") (pin "30") (pinfunction "VDD18_30") (pintype "passive"))
      (node (ref "Q9") (pin "32") (pinfunction "VDDIO_32") (pintype "passive"))
      (node (ref "R69") (pin "1") (pinfunction "1_1") (pintype "passive"))
      (node (ref "R70") (pin "1") (pinfunction "1_1") (pintype "passive"))
      (node (ref "R80") (pin "1") (pinfunction "1_1") (pintype "passive"))
    )
    (net (code "79") (name "3V3") (class "Default")
      (node (ref "C131") (pin "2") (pinfunction "2_2") (pintype "passive"))
      (node (ref "C35") (pin "2") (pinfunction "2_2") (pintype "passive"))
      (node (ref "C36") (pin "2") (pinfunction "2_2") (pintype "passive"))
      (node (ref "C37") (pin "2") (pinfunction "2_2") (pintype "passive"))
      (node (ref "J5") (pin "14") (pinfunction "Y+_14") (pintype "passive"))
      (node (ref "J5") (pin "16") (pinfunction "GO+_16") (pintype "passive"))
      (node (ref "Q15") (pin "4") (pinfunction "VCC_4") (pintype "passive"))
      (node (ref "Q8") (pin "20") (pinfunction "VDD33_20") (pintype "passive"))
      (node (ref "Q8") (pin "21") (pinfunction "VBAT_21") (pintype "passive"))
      (node (ref "Q9") (pin "20") (pinfunction "VDD33_20") (pintype "passive"))
      (node (ref "Q9") (pin "21") (pinfunction "VBAT_21") (pintype "passive"))
      (node (ref "R81") (pin "2") (pinfunction "2_2") (pintype "passive"))
      (node (ref "T1") (pin "3") (pinfunction "S_3") (pintype "passive"))
    )
    (net (code "80") (name "5V") (class "Default")
      (node (ref "C133") (pin "2") (pinfunction "2_2") (pintype "passive"))
      (node (ref "C24") (pin "2") (pinfunction "2_2") (pintype "passive"))
      (node (ref "C25") (pin "2") (pinfunction "2_2") (pintype "passive"))
      (node (ref "Q12") (pin "2") (pinfunction "IN_2") (pintype "passive"))
      (node (ref "Q12") (pin "3") (pinfunction "IN_3") (pintype "passive"))
      (node (ref "Q14") (pin "2") (pinfunction "IN_2") (pintype "passive"))
      (node (ref "Q14") (pin "3") (pinfunction "IN_3") (pintype "passive"))
      (node (ref "Q17") (pin "1") (pinfunction "VIN_1") (pintype "passive"))
      (node (ref "Q17") (pin "3") (pinfunction "EN_3") (pintype "passive"))
    )
    (net (code "81") (name "A3V3") (class "Default")
      (node (ref "C134") (pin "2") (pinfunction "2_2") (pintype "passive"))
      (node (ref "C47") (pin "2") (pinfunction "2_2") (pintype "passive"))
      (node (ref "C48") (pin "2") (pinfunction "2_2") (pintype "passive"))
      (node (ref "Q10") (pin "1") (pinfunction "A3V3_1") (pintype "passive"))
      (node (ref "Q10") (pin "12") (pinfunction "A3V3_12") (pintype "passive"))
      (node (ref "Q17") (pin "5") (pinfunction "VOUT_5") (pintype "passive"))
    )
    (net (code "82") (name "ETHA1V2") (class "Default")
      (node (ref "C129") (pin "2") (pinfunction "2_2") (pintype "passive"))
      (node (ref "C132") (pin "2") (pinfunction "2_2") (pintype "passive"))
      (node (ref "C32") (pin "2") (pinfunction "2_2") (pintype "passive"))
      (node (ref "C33") (pin "2") (pinfunction "2_2") (pintype "passive"))
      (node (ref "L2") (pin "1") (pinfunction "1_1") (pintype "passive"))
      (node (ref "L3") (pin "2") (pinfunction "2_2") (pintype "passive"))
      (node (ref "Q10") (pin "4") (pinfunction "A1V2_4") (pintype "passive"))
      (node (ref "Q10") (pin "9") (pinfunction "A1V2_9") (pintype "passive"))
      (node (ref "T1") (pin "2") (pinfunction "D_2") (pintype "passive"))
      (node (ref "T1") (pin "4") (pinfunction "D_4") (pintype "passive"))
    )
    (net (code "83") (name "ETHD1V2") (class "Default")
      (node (ref "C127") (pin "1") (pinfunction "1_1") (pintype "passive"))
      (node (ref "C128") (pin "2") (pinfunction "2_2") (pintype "passive"))
      (node (ref "C26") (pin "2") (pinfunction "2_2") (pintype "passive"))
      (node (ref "C27") (pin "2") (pinfunction "2_2") (pintype "passive"))
      (node (ref "C28") (pin "2") (pinfunction "2_2") (pintype "passive"))
      (node (ref "C29") (pin "2") (pinfunction "2_2") (pintype "passive"))
      (node (ref "C30") (pin "2") (pinfunction "2_2") (pintype "passive"))
      (node (ref "C31") (pin "2") (pinfunction "2_2") (pintype "passive"))
      (node (ref "L3") (pin "1") (pinfunction "1_1") (pintype "passive"))
      (node (ref "Q10") (pin "14") (pinfunction "D1V2_14") (pintype "passive"))
      (node (ref "Q10") (pin "18") (pinfunction "D1V2_18") (pintype "passive"))
      (node (ref "Q10") (pin "23") (pinfunction "D1V2_23") (pintype "passive"))
      (node (ref "Q10") (pin "26") (pinfunction "D1V2_26") (pintype "passive"))
      (node (ref "Q10") (pin "30") (pinfunction "D1V2_30") (pintype "passive"))
      (node (ref "Q10") (pin "39") (pinfunction "D1V2_39") (pintype "passive"))
    )
    (net (code "84") (name "ETHPLL") (class "Default")
      (node (ref "C130") (pin "2") (pinfunction "2_2") (pintype "passive"))
      (node (ref "C34") (pin "2") (pinfunction "2_2") (pintype "passive"))
      (node (ref "L2") (pin "2") (pinfunction "2_2") (pintype "passive"))
      (node (ref "Q10") (pin "44") (pinfunction "VCCPLL_44") (pintype "passive"))
    )
    (net (code "85") (name "GND") (class "Default")
      (node (ref "C127") (pin "2") (pinfunction "2_2") (pintype "passive"))
      (node (ref "C128") (pin "1") (pinfunction "1_1") (pintype "passive"))
      (node (ref "C129") (pin "1") (pinfunction "1_1") (pintype "passive"))
      (node (ref "C130") (pin "1") (pinfunction "1_1") (pintype "passive"))
      (node (ref "C131") (pin "1") (pinfunction "1_1") (pintype "passive"))
      (node (ref "C132") (pin "1") (pinfunction "1_1") (pintype "passive"))
      (node (ref "C133") (pin "1") (pinfunction "1_1") (pintype "passive"))
      (node (ref "C134") (pin "1") (pinfunction "1_1") (pintype "passive"))
      (node (ref "C186") (pin "1") (pinfunction "1_1") (pintype "passive"))
      (node (ref "C187") (pin "2") (pinfunction "2_2") (pintype "passive"))
      (node (ref "C196") (pin "1") (pinfunction "1_1") (pintype "passive"))
      (node (ref "C197") (pin "1") (pinfunction "1_1") (pintype "passive"))
      (node (ref "C198") (pin "1") (pinfunction "1_1") (pintype "passive"))
      (node (ref "C22") (pin "1") (pinfunction "1_1") (pintype "passive"))
      (node (ref "C23") (pin "1") (pinfunction "1_1") (pintype "passive"))
      (node (ref "C24") (pin "1") (pinfunction "1_1") (pintype "passive"))
      (node (ref "C25") (pin "1") (pinfunction "1_1") (pintype "passive"))
      (node (ref "C26") (pin "1") (pinfunction "1_1") (pintype "passive"))
      (node (ref "C27") (pin "1") (pinfunction "1_1") (pintype "passive"))
      (node (ref "C28") (pin "1") (pinfunction "1_1") (pintype "passive"))
      (node (ref "C29") (pin "1") (pinfunction "1_1") (pintype "passive"))
      (node (ref "C30") (pin "1") (pinfunction "1_1") (pintype "passive"))
      (node (ref "C31") (pin "1") (pinfunction "1_1") (pintype "passive"))
      (node (ref "C32") (pin "1") (pinfunction "1_1") (pintype "passive"))
      (node (ref "C33") (pin "1") (pinfunction "1_1") (pintype "passive"))
      (node (ref "C34") (pin "1") (pinfunction "1_1") (pintype "passive"))
      (node (ref "C35") (pin "1") (pinfunction "1_1") (pintype "passive"))
      (node (ref "C36") (pin "1") (pinfunction "1_1") (pintype "passive"))
      (node (ref "C37") (pin "1") (pinfunction "1_1") (pintype "passive"))
      (node (ref "C38") (pin "1") (pinfunction "1_1") (pintype "passive"))
      (node (ref "C39") (pin "1") (pinfunction "1_1") (pintype "passive"))
      (node (ref "C40") (pin "1") (pinfunction "1_1") (pintype "passive"))
      (node (ref "C41") (pin "1") (pinfunction "1_1") (pintype "passive"))
      (node (ref "C42") (pin "1") (pinfunction "1_1") (pintype "passive"))
      (node (ref "C43") (pin "1") (pinfunction "1_1") (pintype "passive"))
      (node (ref "C44") (pin "1") (pinfunction "1_1") (pintype "passive"))
      (node (ref "C45") (pin "1") (pinfunction "1_1") (pintype "passive"))
      (node (ref "C46") (pin "1") (pinfunction "1_1") (pintype "passive"))
      (node (ref "C47") (pin "1") (pinfunction "1_1") (pintype "passive"))
      (node (ref "C48") (pin "1") (pinfunction "1_1") (pintype "passive"))
      (node (ref "C49") (pin "2") (pinfunction "2_2") (pintype "passive"))
      (node (ref "C50") (pin "1") (pinfunction "1_1") (pintype "passive"))
      (node (ref "C51") (pin "1") (pinfunction "1_1") (pintype "passive"))
      (node (ref "C52") (pin "1") (pinfunction "1_1") (pintype "passive"))
      (node (ref "C53") (pin "1") (pinfunction "1_1") (pintype "passive"))
      (node (ref "C54") (pin "1") (pinfunction "1_1") (pintype "passive"))
      (node (ref "J1") (pin "0") (pinfunction "SHIELD_0") (pintype "passive"))
      (node (ref "J1") (pin "4") (pinfunction "GND_4") (pintype "passive"))
      (node (ref "J2") (pin "0") (pinfunction "SHIELD_0") (pintype "passive"))
      (node (ref "J2") (pin "4") (pinfunction "GND_4") (pintype "passive"))
      (node (ref "J5") (pin "0") (pinfunction "GND_0") (pintype "passive"))
      (node (ref "Q10") (pin "29") (pinfunction "GND_29") (pintype "passive"))
      (node (ref "Q10") (pin "49") (pinfunction "GND_49") (pintype "passive"))
      (node (ref "Q11") (pin "2") (pinfunction "GND_2") (pintype "passive"))
      (node (ref "Q12") (pin "1") (pinfunction "GND_1") (pintype "passive"))
      (node (ref "Q13") (pin "2") (pinfunction "GND_2") (pintype "passive"))
      (node (ref "Q14") (pin "1") (pinfunction "GND_1") (pintype "passive"))
      (node (ref "Q15") (pin "2") (pinfunction "GND_2") (pintype "passive"))
      (node (ref "Q17") (pin "2") (pinfunction "GND_2") (pintype "passive"))
      (node (ref "Q8") (pin "14") (pinfunction "CFG_14") (pintype "passive"))
      (node (ref "Q8") (pin "33") (pinfunction "GND_33") (pintype "passive"))
      (node (ref "Q9") (pin "14") (pinfunction "CFG_14") (pintype "passive"))
      (node (ref "Q9") (pin "33") (pinfunction "GND_33") (pintype "passive"))
      (node (ref "R55") (pin "1") (pinfunction "1_1") (pintype "passive"))
      (node (ref "R68") (pin "1") (pinfunction "1_1") (pintype "passive"))
      (node (ref "R73") (pin "1") (pinfunction "1_1") (pintype "passive"))
      (node (ref "R74") (pin "1") (pinfunction "1_1") (pintype "passive"))
      (node (ref "R78") (pin "1") (pinfunction "1_1") (pintype "passive"))
      (node (ref "R79") (pin "1") (pinfunction "1_1") (pintype "passive"))
      (node (ref "Y2") (pin "2") (pinfunction "GND_2") (pintype "passive"))
      (node (ref "Y2") (pin "4") (pinfunction "GND_4") (pintype "passive"))
    )
    (net (code "86") (name "Net-(J5-ACT)") (class "Default")
      (node (ref "C51") (pin "2") (pinfunction "2_2") (pintype "passive"))
      (node (ref "J5") (pin "12") (pinfunction "ACT_12") (pintype "passive"))
    )
    (net (code "87") (name "Net-(J5-BCT)") (class "Default")
      (node (ref "C52") (pin "2") (pinfunction "2_2") (pintype "passive"))
      (node (ref "J5") (pin "6") (pinfunction "BCT_6") (pintype "passive"))
    )
    (net (code "88") (name "Net-(J5-CCT)") (class "Default")
      (node (ref "C53") (pin "2") (pinfunction "2_2") (pintype "passive"))
      (node (ref "J5") (pin "1") (pinfunction "CCT_1") (pintype "passive"))
    )
    (net (code "89") (name "Net-(J5-DCT)") (class "Default")
      (node (ref "C54") (pin "2") (pinfunction "2_2") (pintype "passive"))
      (node (ref "J5") (pin "7") (pinfunction "DCT_7") (pintype "passive"))
    )
    (net (code "90") (name "Net-(J5-G-)") (class "Default")
      (node (ref "J5") (pin "17") (pinfunction "G-_17") (pintype "passive"))
      (node (ref "R76") (pin "1") (pinfunction "1_1") (pintype "passive"))
    )
    (net (code "91") (name "Net-(J5-O-)") (class "Default")
      (node (ref "J5") (pin "15") (pinfunction "O-_15") (pintype "passive"))
      (node (ref "R77") (pin "1") (pinfunction "1_1") (pintype "passive"))
    )
    (net (code "92") (name "Net-(J5-Y-)") (class "Default")
      (node (ref "J5") (pin "13") (pinfunction "Y-_13") (pintype "passive"))
      (node (ref "R132") (pin "1") (pinfunction "1_1") (pintype "passive"))
    )
    (net (code "93") (name "Net-(Q8B-VDD15)") (class "Default")
      (node (ref "C49") (pin "1") (pinfunction "1_1") (pintype "passive"))
      (node (ref "Q8") (pin "12") (pinfunction "VDD15_12") (pintype "passive"))
    )
    (net (code "94") (name "Net-(Q9B-VDD15)") (class "Default")
      (node (ref "C50") (pin "2") (pinfunction "2_2") (pintype "passive"))
      (node (ref "Q9") (pin "12") (pinfunction "VDD15_12") (pintype "passive"))
    )
    (net (code "95") (name "Net-(Q10A-ISET)") (class "Default")
      (node (ref "Q10") (pin "48") (pinfunction "ISET_48") (pintype "passive"))
      (node (ref "R55") (pin "2") (pinfunction "2_2") (pintype "passive"))
    )
    (net (code "96") (name "Net-(Q10A-XI)") (class "Default")
      (node (ref "C196") (pin "2") (pinfunction "2_2") (pintype "passive"))
      (node (ref "Q10") (pin "46") (pinfunction "XI_46") (pintype "passive"))
      (node (ref "Y2") (pin "1") (pinfunction "X_1") (pintype "passive"))
    )
    (net (code "97") (name "Net-(Q10A-XO)") (class "Default")
      (node (ref "C197") (pin "2") (pinfunction "2_2") (pintype "passive"))
      (node (ref "Q10") (pin "45") (pinfunction "XO_45") (pintype "passive"))
      (node (ref "Y2") (pin "3") (pinfunction "X_3") (pintype "passive"))
    )
    (net (code "98") (name "Net-(Q12-EN)") (class "Default")
      (node (ref "Q12") (pin "4") (pinfunction "EN_4") (pintype "passive"))
      (node (ref "Q8") (pin "17") (pinfunction "CPEN_17") (pintype "passive"))
    )
    (net (code "99") (name "Net-(Q14-EN)") (class "Default")
      (node (ref "Q14") (pin "4") (pinfunction "EN_4") (pintype "passive"))
      (node (ref "Q9") (pin "17") (pinfunction "CPEN_17") (pintype "passive"))
    )
    (net (code "100") (name "Net-(Q15-CLK)") (class "Default")
      (node (ref "Q15") (pin "3") (pinfunction "CLK_3") (pintype "passive"))
      (node (ref "R75") (pin "1") (pinfunction "1_1") (pintype "passive"))
    )
    (net (code "101") (name "Net-(Q17-BYPASS)") (class "Default")
      (node (ref "C198") (pin "2") (pinfunction "2_2") (pintype "passive"))
      (node (ref "Q17") (pin "4") (pinfunction "BYPASS_4") (pintype "passive"))
    )
    (net (code "102") (name "unconnected-(Q8A-ID-Pad23)") (class "Default")
      (node (ref "Q8") (pin "23") (pinfunction "ID_23") (pintype "passive"))
    )
    (net (code "103") (name "unconnected-(Q9A-ID-Pad23)") (class "Default")
      (node (ref "Q9") (pin "23") (pinfunction "ID_23") (pintype "passive"))
    )
    (net (code "104") (name "unconnected-(Q15-EN-Pad1)") (class "Default")
      (node (ref "Q15") (pin "1") (pinfunction "EN_1") (pintype "passive"))
    )
  )
)
